# Power_Supply.net
KiCad netlist of a schematic drawn in Altium Designer
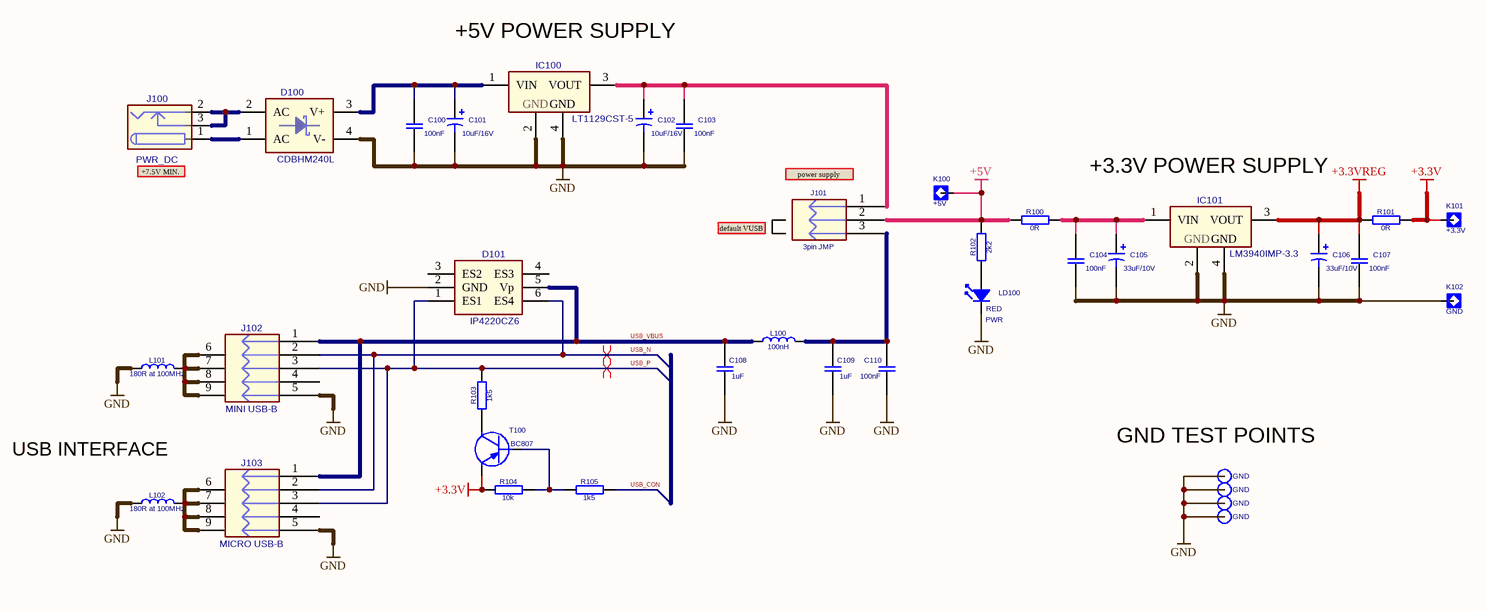
[diagram p0: Power Supply.SchDoc]

(export (version "E")
  (design (tool "Eeschema 10.0.6"))
  (components
    (comp (ref "C100")
      (value "100nF")
      (footprint "Y0603")
      (description "CAPC0603")
      (libsource (lib "ALT_CP") (part "CAPC0603"))
    )
    (comp (ref "C101")
      (value "10uF/16V")
      (footprint "ALT_CP:CAP_TANT_1206_CASE-A")
      (description "C_TANTAL_1206")
      (libsource (lib "ALT_CP") (part "C_TANTAL_1206"))
    )
    (comp (ref "C102")
      (value "10uF/16V")
      (footprint "ALT_CP:CAP_TANT_1206_CASE-A")
      (description "C_TANTAL_1206")
      (libsource (lib "ALT_CP") (part "C_TANTAL_1206"))
    )
    (comp (ref "C103")
      (value "100nF")
      (footprint "Y0603")
      (description "CAPC0603")
      (libsource (lib "ALT_CP") (part "CAPC0603"))
    )
    (comp (ref "C104")
      (value "100nF")
      (footprint "Y0603")
      (description "CAPC0603")
      (libsource (lib "ALT_CP") (part "CAPC0603"))
    )
    (comp (ref "C105")
      (value "33uF/10V")
      (footprint "ALT_CP:C_TANTAL_B")
      (description "C_TANTAL_B")
      (libsource (lib "ALT_CP") (part "C_TANTAL_B"))
    )
    (comp (ref "C106")
      (value "33uF/10V")
      (footprint "ALT_CP:C_TANTAL_B")
      (description "C_TANTAL_B")
      (libsource (lib "ALT_CP") (part "C_TANTAL_B"))
    )
    (comp (ref "C107")
      (value "100nF")
      (footprint "Y0603")
      (description "CAPC0603")
      (libsource (lib "ALT_CP") (part "CAPC0603"))
    )
    (comp (ref "C108")
      (value "1uF")
      (footprint "Y0603")
      (description "CAPC0603")
      (libsource (lib "ALT_CP") (part "CAPC0603"))
    )
    (comp (ref "C109")
      (value "1uF")
      (footprint "Y0603")
      (description "CAPC0603")
      (libsource (lib "ALT_CP") (part "CAPC0603"))
    )
    (comp (ref "C110")
      (value "100nF")
      (footprint "Y0603")
      (description "CAPC0603")
      (libsource (lib "ALT_CP") (part "CAPC0603"))
    )
    (comp (ref "D100")
      (value "CDBHM240L")
      (footprint "ALT_CP:GRETZ_MBS2")
      (description "GRETZ_MBS2_Schottky")
      (libsource (lib "ALT_CP") (part "GRETZ_MBS2"))
    )
    (comp (ref "D101")
      (value "IP4220CZ6")
      (footprint "SOT-457")
      (description "D_IP4220CZ6")
      (libsource (lib "ALT_CP") (part "D_IP4220CZ6"))
    )
    (comp (ref "IC100")
      (value "LT1129CST-5")
      (footprint "ALT_CP:SOT-223-3")
      (libsource (lib "ALT_CP") (part "LM3940-3.3"))
    )
    (comp (ref "IC101")
      (value "LM3940IMP-3.3")
      (footprint "ALT_CP:SOT-223-3")
      (description "LM3940-3.3")
      (libsource (lib "ALT_CP") (part "LM3940-3.3"))
    )
    (comp (ref "J100")
      (value "PWR_DC")
      (footprint "ALT_CP:CON_JCK_2.5mm")
      (description "PWR_JACK_2.1mm x 5.5mm")
      (fields (field (name "Comment") "PWR_DC_PJ-202A"))
      (libsource (lib "ALT_CP") (part "CON_JCK_2.5mm"))
    )
    (comp (ref "J101")
      (value "3pin JMP")
      (footprint "ALT_CP:CON3M-LINE")
      (description "CON3M_LINE")
      (libsource (lib "ALT_CP") (part "CON3M_LINE"))
    )
    (comp (ref "J102")
      (value "MINI USB-B")
      (footprint "ALT_CP:CON_USB-B-MINI_SD-67503-010_5075BMR-05-SM-CR")
      (description "CON_USB_B_RA")
      (libsource (lib "ALT_CP") (part "CON_USB_B_RA"))
    )
    (comp (ref "J103")
      (value "MICRO USB-B")
      (footprint "ALT_CP:CON_USB_MICRO_B_WE-629 105 136 821")
      (description "CON_USB_MICRO_B")
      (libsource (lib "ALT_CP") (part "CON_USB_MICRO_B"))
    )
    (comp (ref "K100")
      (value "+5V")
      (footprint "ALT_CP:TESTP_ROUND_1.0mm")
      (description "TP1")
      (libsource (lib "ALT_CP") (part "TP1"))
    )
    (comp (ref "K101")
      (value "+3.3V")
      (footprint "ALT_CP:TESTP_ROUND_1.0mm")
      (description "TP1")
      (libsource (lib "ALT_CP") (part "TP1"))
    )
    (comp (ref "K102")
      (value "GND")
      (footprint "ALT_CP:TESTP_ROUND_1.0mm")
      (description "TP1")
      (libsource (lib "ALT_CP") (part "TP1"))
    )
    (comp (ref "K103")
      (value "GND")
      (footprint "CON1_PIN_Round_1.0x1.8mm")
      (description "TP_1.0mm")
      (libsource (lib "ALT_CP") (part "TP_1.0mm"))
    )
    (comp (ref "K104")
      (value "GND")
      (footprint "CON1_PIN_Round_1.0x1.8mm")
      (description "TP_1.0mm")
      (libsource (lib "ALT_CP") (part "TP_1.0mm"))
    )
    (comp (ref "K105")
      (value "GND")
      (footprint "CON1_PIN_Round_1.0x1.8mm")
      (description "TP_1.0mm")
      (libsource (lib "ALT_CP") (part "TP_1.0mm"))
    )
    (comp (ref "K106")
      (value "GND")
      (footprint "CON1_PIN_Round_1.0x1.8mm")
      (description "TP_1.0mm")
      (libsource (lib "ALT_CP") (part "TP_1.0mm"))
    )
    (comp (ref "L100")
      (value "100nH")
      (footprint "ALT_CP:INDCC_1812")
      (description "INDC1812")
      (libsource (lib "ALT_CP") (part "INDC1812"))
    )
    (comp (ref "L101")
      (value "180R at 100MHz")
      (footprint "ALT_CP:Y0603")
      (description "INDC0603")
      (fields (field (name "Comment") "BLM18PG181SN1"))
      (libsource (lib "ALT_CP") (part "INDC0603"))
    )
    (comp (ref "L102")
      (value "180R at 100MHz")
      (footprint "ALT_CP:Y0603")
      (description "INDC0603")
      (fields (field (name "Comment") "BLM18PG181SN1"))
      (libsource (lib "ALT_CP") (part "INDC0603"))
    )
    (comp (ref "LD100")
      (value "RED")
      (footprint "ALT_CP:LED_0603")
      (description "LEDY0603")
      (fields (field (name "ALTIUM_UNNAMED_1") "PWR"))
      (libsource (lib "ALT_CP") (part "LEDY0603"))
    )
    (comp (ref "R100")
      (value "0R")
      (footprint "Y0603")
      (description "RESC0603")
      (libsource (lib "ALT_CP") (part "RESC0603"))
    )
    (comp (ref "R101")
      (value "0R")
      (footprint "Y0603")
      (description "RESC0603")
      (libsource (lib "ALT_CP") (part "RESC0603"))
    )
    (comp (ref "R102")
      (value "2k2")
      (footprint "Y0603")
      (description "RESC0603")
      (libsource (lib "ALT_CP") (part "RESC0603"))
    )
    (comp (ref "R103")
      (value "1k5")
      (footprint "Y0603")
      (description "RESC0603")
      (libsource (lib "ALT_CP") (part "RESC0603"))
    )
    (comp (ref "R104")
      (value "10k")
      (footprint "Y0603")
      (description "RESC0603")
      (libsource (lib "ALT_CP") (part "RESC0603"))
    )
    (comp (ref "R105")
      (value "1k5")
      (footprint "Y0603")
      (description "RESC0603")
      (libsource (lib "ALT_CP") (part "RESC0603"))
    )
    (comp (ref "T100") (value "BC807") (footprint "SOT-23") (libsource (lib "ALT_CP") (part "BC807")))
  )
  (nets
    (net (code "1") (name "+3.3V") (class "Default")
      (node (ref "K101") (pin "1") (pintype "passive"))
      (node (ref "R101") (pin "1") (pintype "passive"))
      (node (ref "R104") (pin "2") (pintype "passive"))
      (node (ref "T100") (pin "2") (pinfunction "E_2") (pintype "passive"))
    )
    (net (code "2") (name "+3.3VREG") (class "Default")
      (node (ref "C106") (pin "1") (pinfunction "1_1") (pintype "passive"))
      (node (ref "C107") (pin "1") (pintype "passive"))
      (node (ref "IC101") (pin "3") (pinfunction "VOUT_3") (pintype "passive"))
      (node (ref "R101") (pin "2") (pintype "passive"))
    )
    (net (code "3") (name "+5V") (class "Default")
      (node (ref "J101") (pin "2") (pinfunction "P2_2") (pintype "passive"))
      (node (ref "K100") (pin "1") (pintype "passive"))
      (node (ref "R100") (pin "2") (pintype "passive"))
      (node (ref "R102") (pin "2") (pintype "passive"))
    )
    (net (code "4") (name "/USB_CON") (class "Default") (node (ref "R105") (pin "1") (pintype "passive")))
    (net (code "5") (name "/USB_N") (class "Default")
      (node (ref "D101") (pin "6") (pinfunction "ES4_6") (pintype "passive"))
      (node (ref "J102") (pin "2") (pinfunction "D-_2") (pintype "passive"))
      (node (ref "J103") (pin "2") (pinfunction "D-_2") (pintype "passive"))
    )
    (net (code "6") (name "/USB_P") (class "Default")
      (node (ref "D101") (pin "1") (pinfunction "ES1_1") (pintype "passive"))
      (node (ref "J102") (pin "3") (pinfunction "D+_3") (pintype "passive"))
      (node (ref "J103") (pin "3") (pinfunction "D+_3") (pintype "passive"))
      (node (ref "R103") (pin "1") (pintype "passive"))
    )
    (net (code "7") (name "/USB_VBUS") (class "Default")
      (node (ref "C108") (pin "1") (pintype "passive"))
      (node (ref "D101") (pin "5") (pinfunction "Vp_5") (pintype "passive"))
      (node (ref "J102") (pin "1") (pinfunction "VBUS_1") (pintype "passive"))
      (node (ref "J103") (pin "1") (pinfunction "VBUS_1") (pintype "passive"))
      (node (ref "L100") (pin "1") (pintype "passive"))
    )
    (net (code "8") (name "GND") (class "Default")
      (node (ref "C100") (pin "2") (pintype "passive"))
      (node (ref "C101") (pin "2") (pinfunction "2_2") (pintype "passive"))
      (node (ref "C102") (pin "2") (pinfunction "2_2") (pintype "passive"))
      (node (ref "C103") (pin "2") (pintype "passive"))
      (node (ref "C104") (pin "2") (pintype "passive"))
      (node (ref "C105") (pin "2") (pinfunction "2_2") (pintype "passive"))
      (node (ref "C106") (pin "2") (pinfunction "2_2") (pintype "passive"))
      (node (ref "C107") (pin "2") (pintype "passive"))
      (node (ref "C108") (pin "2") (pintype "passive"))
      (node (ref "C109") (pin "2") (pintype "passive"))
      (node (ref "C110") (pin "2") (pintype "passive"))
      (node (ref "D100") (pin "4") (pinfunction "V-_4") (pintype "passive"))
      (node (ref "D101") (pin "2") (pinfunction "GND_2") (pintype "passive"))
      (node (ref "IC100") (pin "2") (pinfunction "GND_2") (pintype "passive"))
      (node (ref "IC100") (pin "4") (pinfunction "GND_4") (pintype "passive"))
      (node (ref "IC101") (pin "2") (pinfunction "GND_2") (pintype "passive"))
      (node (ref "IC101") (pin "4") (pinfunction "GND_4") (pintype "passive"))
      (node (ref "J102") (pin "5") (pinfunction "GND_5") (pintype "passive"))
      (node (ref "J103") (pin "5") (pinfunction "GND_5") (pintype "passive"))
      (node (ref "K102") (pin "1") (pintype "passive"))
      (node (ref "K103") (pin "1") (pintype "passive"))
      (node (ref "K104") (pin "1") (pintype "passive"))
      (node (ref "K105") (pin "1") (pintype "passive"))
      (node (ref "K106") (pin "1") (pintype "passive"))
      (node (ref "L101") (pin "1") (pintype "passive"))
      (node (ref "L102") (pin "1") (pintype "passive"))
      (node (ref "LD100") (pin "1") (pintype "passive"))
    )
    (net (code "9") (name "Net-(D100-AC-Pad1)") (class "Default")
      (node (ref "D100") (pin "1") (pinfunction "AC_1") (pintype "passive"))
      (node (ref "J100") (pin "1") (pinfunction "1_1") (pintype "power_in"))
    )
    (net (code "10") (name "Net-(D100-AC-Pad2)") (class "Default")
      (node (ref "D100") (pin "2") (pinfunction "AC_2") (pintype "passive"))
      (node (ref "J100") (pin "2") (pinfunction "2_2") (pintype "power_in"))
      (node (ref "J100") (pin "3") (pinfunction "3_3") (pintype "power_in"))
    )
    (net (code "11") (name "Net-(D100-V+)") (class "Default")
      (node (ref "C100") (pin "1") (pintype "passive"))
      (node (ref "C101") (pin "1") (pinfunction "1_1") (pintype "passive"))
      (node (ref "D100") (pin "3") (pinfunction "V+_3") (pintype "passive"))
      (node (ref "IC100") (pin "1") (pinfunction "VIN_1") (pintype "passive"))
    )
    (net (code "12") (name "Net-(IC100-VOUT)") (class "Default")
      (node (ref "C102") (pin "1") (pinfunction "1_1") (pintype "passive"))
      (node (ref "C103") (pin "1") (pintype "passive"))
      (node (ref "IC100") (pin "3") (pinfunction "VOUT_3") (pintype "passive"))
      (node (ref "J101") (pin "1") (pinfunction "P1_1") (pintype "passive"))
    )
    (net (code "13") (name "Net-(IC101-VIN)") (class "Default")
      (node (ref "C104") (pin "1") (pintype "passive"))
      (node (ref "C105") (pin "1") (pinfunction "1_1") (pintype "passive"))
      (node (ref "IC101") (pin "1") (pinfunction "VIN_1") (pintype "passive"))
      (node (ref "R100") (pin "1") (pintype "passive"))
    )
    (net (code "14") (name "Net-(J101-P3)") (class "Default")
      (node (ref "C109") (pin "1") (pintype "passive"))
      (node (ref "C110") (pin "1") (pintype "passive"))
      (node (ref "J101") (pin "3") (pinfunction "P3_3") (pintype "passive"))
      (node (ref "L100") (pin "2") (pintype "passive"))
    )
    (net (code "15") (name "Net-(J102-Case1)") (class "Default")
      (node (ref "J102") (pin "6") (pinfunction "Case1_6") (pintype "passive"))
      (node (ref "J102") (pin "7") (pinfunction "Case2_7") (pintype "passive"))
      (node (ref "J102") (pin "8") (pinfunction "Case3_8") (pintype "passive"))
      (node (ref "J102") (pin "9") (pinfunction "Case4_9") (pintype "passive"))
      (node (ref "L101") (pin "2") (pintype "passive"))
    )
    (net (code "16") (name "Net-(J103-Case1)") (class "Default")
      (node (ref "J103") (pin "6") (pinfunction "Case1_6") (pintype "passive"))
      (node (ref "J103") (pin "7") (pinfunction "Case2_7") (pintype "passive"))
      (node (ref "J103") (pin "8") (pinfunction "Case3_8") (pintype "passive"))
      (node (ref "J103") (pin "9") (pinfunction "Case4_9") (pintype "passive"))
      (node (ref "L102") (pin "2") (pintype "passive"))
    )
    (net (code "17") (name "Net-(LD100-Pad2)") (class "Default")
      (node (ref "LD100") (pin "2") (pintype "passive"))
      (node (ref "R102") (pin "1") (pintype "passive"))
    )
    (net (code "18") (name "Net-(T100-B)") (class "Default")
      (node (ref "R104") (pin "1") (pintype "passive"))
      (node (ref "R105") (pin "2") (pintype "passive"))
      (node (ref "T100") (pin "1") (pinfunction "B_1") (pintype "passive"))
    )
    (net (code "19") (name "Net-(T100-C)") (class "Default")
      (node (ref "R103") (pin "2") (pintype "passive"))
      (node (ref "T100") (pin "3") (pinfunction "C_3") (pintype "passive"))
    )
    (net (code "20") (name "unconnected-(D101-ES2-Pad3)") (class "Default")
      (node (ref "D101") (pin "3") (pinfunction "ES2_3") (pintype "passive"))
    )
    (net (code "21") (name "unconnected-(D101-ES3-Pad4)") (class "Default")
      (node (ref "D101") (pin "4") (pinfunction "ES3_4") (pintype "passive"))
    )
    (net (code "22") (name "unconnected-(J102-ID-Pad4)") (class "Default")
      (node (ref "J102") (pin "4") (pinfunction "ID_4") (pintype "passive"))
    )
    (net (code "23") (name "unconnected-(J103-ID-Pad4)") (class "Default")
      (node (ref "J103") (pin "4") (pinfunction "ID_4") (pintype "passive"))
    )
  )
)
